# PennyMan_Ard_R3_Shield_v9_3.net
KiCad netlist of a schematic drawn in EAGLE
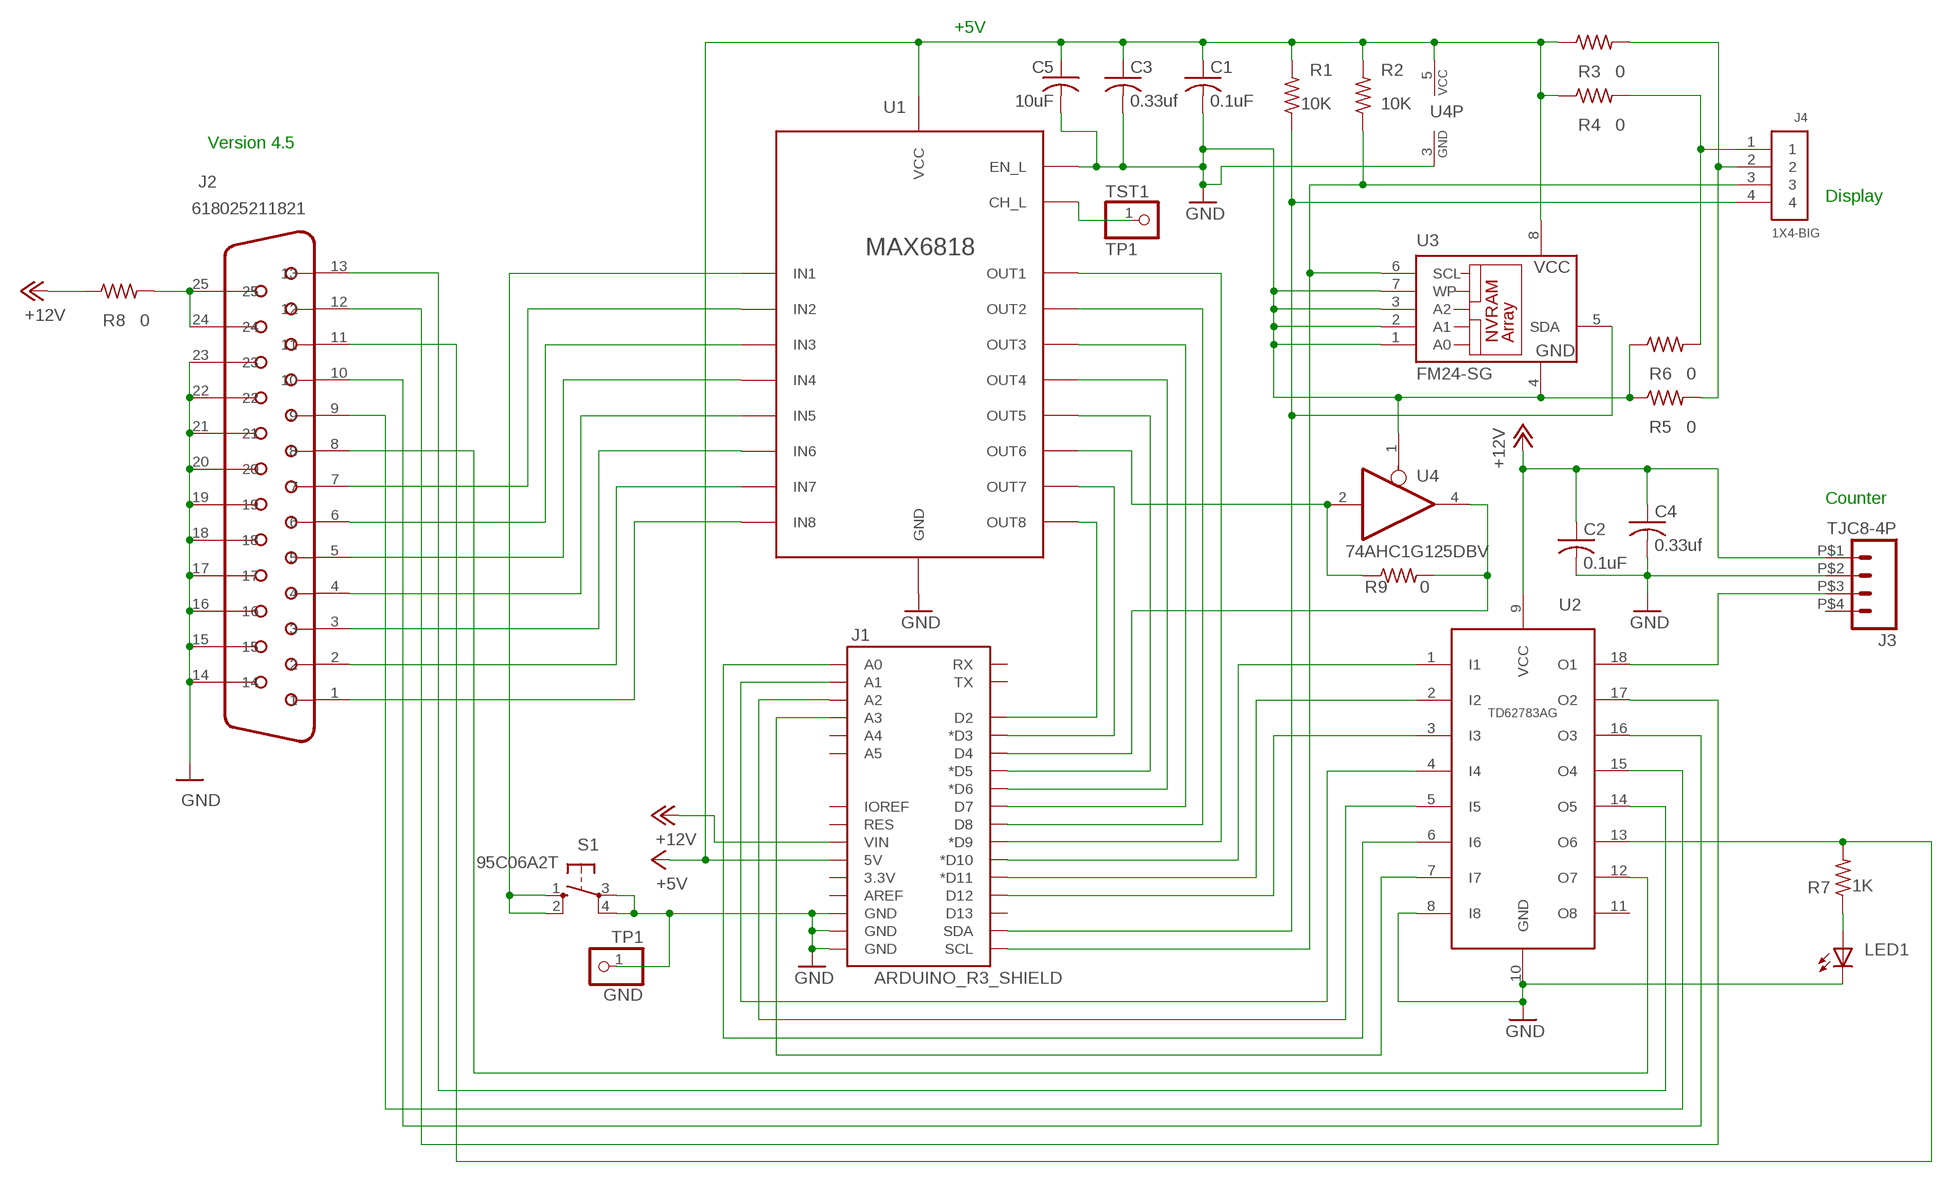
[diagram p0: schematic, sheet 1]

(export (version "E")
  (design (tool "Eeschema 10.0.6"))
  (components
    (comp (ref "C1")
      (value "0.1uF")
      (footprint "eagle-import:C0805")
      (libsource (lib "eagle-import") (part "C-USC0805"))
    )
    (comp (ref "C2")
      (value "0.1uF")
      (footprint "eagle-import:C0805")
      (libsource (lib "eagle-import") (part "C-USC0805"))
    )
    (comp (ref "C3")
      (value "0.33uf")
      (footprint "eagle-import:C1206")
      (libsource (lib "eagle-import") (part "C-USC1206"))
    )
    (comp (ref "C4")
      (value "0.33uf")
      (footprint "eagle-import:C1206")
      (libsource (lib "eagle-import") (part "C-USC1206"))
    )
    (comp (ref "C5")
      (value "10uF")
      (footprint "eagle-import:C1812")
      (libsource (lib "eagle-import") (part "C-USC1812"))
    )
    (comp (ref "GND")
      (value "TP1")
      (footprint "eagle-import:1X01")
      (libsource (lib "eagle-import") (part "PINHD-1X1"))
    )
    (comp (ref "J1")
      (value "ARDUINO_R3_SHIELD")
      (footprint "eagle-import:UNO_R3_SHIELD")
      (libsource (lib "eagle-import") (part "ARDUINO_R3_SHIELD"))
    )
    (comp (ref "J2")
      (value "618025211821")
      (footprint "eagle-import:618025211821")
      (libsource (lib "eagle-import") (part "618025211821"))
    )
    (comp (ref "J3")
      (value "TJC8-4P")
      (footprint "eagle-import:TJC8-4P")
      (libsource (lib "eagle-import") (part "TJC8-4P"))
    )
    (comp (ref "J4")
      (value "1X4-BIG")
      (footprint "eagle-import:1X04-BIG")
      (libsource (lib "eagle-import") (part "1X4-BIG"))
    )
    (comp (ref "LED1")
      (value "LEDSML0805")
      (footprint "eagle-import:SML0805")
      (libsource (lib "eagle-import") (part "LEDSML0805"))
    )
    (comp (ref "R1")
      (value "10K")
      (footprint "eagle-import:R0805")
      (libsource (lib "eagle-import") (part "R-US_R0805"))
    )
    (comp (ref "R2")
      (value "10K")
      (footprint "eagle-import:R0805")
      (libsource (lib "eagle-import") (part "R-US_R0805"))
    )
    (comp (ref "R3")
      (value "0")
      (footprint "eagle-import:R0805")
      (libsource (lib "eagle-import") (part "R-US_R0805"))
    )
    (comp (ref "R4")
      (value "0")
      (footprint "eagle-import:R0805")
      (libsource (lib "eagle-import") (part "R-US_R0805"))
    )
    (comp (ref "R5")
      (value "0")
      (footprint "eagle-import:R0805")
      (libsource (lib "eagle-import") (part "R-US_R0805"))
    )
    (comp (ref "R6")
      (value "0")
      (footprint "eagle-import:R0805")
      (libsource (lib "eagle-import") (part "R-US_R0805"))
    )
    (comp (ref "R7")
      (value "1K")
      (footprint "eagle-import:R0805")
      (libsource (lib "eagle-import") (part "R-US_R0805"))
    )
    (comp (ref "R8")
      (value "0")
      (footprint "eagle-import:R0805")
      (libsource (lib "eagle-import") (part "R-US_R0805"))
    )
    (comp (ref "R9")
      (value "0")
      (footprint "eagle-import:R0805")
      (libsource (lib "eagle-import") (part "R-US_R0805"))
    )
    (comp (ref "S1")
      (value "95C06A2T")
      (footprint "eagle-import:B3F-10XX")
      (libsource (lib "eagle-import") (part "10-XX"))
    )
    (comp (ref "TST1")
      (value "TP1")
      (footprint "eagle-import:1X01")
      (libsource (lib "eagle-import") (part "PINHD-1X1"))
    )
    (comp (ref "U1")
      (value "MAX6818")
      (footprint "eagle-import:SSOP20")
      (libsource (lib "eagle-import") (part "MAX6818"))
    )
    (comp (ref "U2")
      (value "TD62783AG")
      (footprint "eagle-import:SOP18")
      (libsource (lib "eagle-import") (part "TD62783AG"))
    )
    (comp (ref "U3")
      (value "FM24-SG")
      (footprint "eagle-import:SO8")
      (libsource (lib "eagle-import") (part "FM24-SG"))
    )
    (comp (ref "U4")
      (value "74AHC1G125DBV")
      (footprint "eagle-import:SOT23-5")
      (libsource (lib "eagle-import") (part "741G125DBVAHC"))
    )
  )
  (nets
    (net (code "1") (name "+5V") (class "Default")
      (node (ref "C1") (pin "1") (pinfunction "1_1") (pintype "passive"))
      (node (ref "C3") (pin "1") (pinfunction "1_1") (pintype "passive"))
      (node (ref "C5") (pin "1") (pinfunction "1_1") (pintype "passive"))
      (node (ref "J1") (pin "5V") (pinfunction "5V_5V") (pintype "bidirectional"))
      (node (ref "R1") (pin "2") (pinfunction "2_2") (pintype "passive"))
      (node (ref "R2") (pin "2") (pinfunction "2_2") (pintype "passive"))
      (node (ref "R3") (pin "1") (pinfunction "1_1") (pintype "passive"))
      (node (ref "R4") (pin "1") (pinfunction "1_1") (pintype "passive"))
      (node (ref "U1") (pin "VCC") (pinfunction "VCC_VCC") (pintype "bidirectional"))
      (node (ref "U3") (pin "8") (pinfunction "VCC_8") (pintype "power_in"))
      (node (ref "U4") (pin "5") (pinfunction "VCC_5") (pintype "power_in"))
    )
    (net (code "2") (name "+12V") (class "Default")
      (node (ref "C2") (pin "1") (pinfunction "1_1") (pintype "passive"))
      (node (ref "C4") (pin "1") (pinfunction "1_1") (pintype "passive"))
      (node (ref "J1") (pin "VIN") (pinfunction "VIN_VIN") (pintype "bidirectional"))
      (node (ref "J3") (pin "P$1") (pinfunction "1_P$1") (pintype "passive"))
      (node (ref "R8") (pin "1") (pinfunction "1_1") (pintype "passive"))
      (node (ref "U2") (pin "9") (pinfunction "VCC_9") (pintype "bidirectional"))
    )
    (net (code "3") (name "GND") (class "Default")
      (node (ref "C1") (pin "2") (pinfunction "2_2") (pintype "passive"))
      (node (ref "C2") (pin "2") (pinfunction "2_2") (pintype "passive"))
      (node (ref "C3") (pin "2") (pinfunction "2_2") (pintype "passive"))
      (node (ref "C4") (pin "2") (pinfunction "2_2") (pintype "passive"))
      (node (ref "C5") (pin "2") (pinfunction "2_2") (pintype "passive"))
      (node (ref "GND") (pin "1") (pinfunction "1_1") (pintype "passive"))
      (node (ref "J1") (pin "GND@0") (pinfunction "GND_GND@0") (pintype "bidirectional"))
      (node (ref "J1") (pin "GND@1") (pinfunction "GND_GND@1") (pintype "bidirectional"))
      (node (ref "J1") (pin "GND@2") (pinfunction "GND_GND@2") (pintype "bidirectional"))
      (node (ref "J2") (pin "14") (pinfunction "14_14") (pintype "bidirectional"))
      (node (ref "J2") (pin "15") (pinfunction "15_15") (pintype "bidirectional"))
      (node (ref "J2") (pin "16") (pinfunction "16_16") (pintype "bidirectional"))
      (node (ref "J2") (pin "17") (pinfunction "17_17") (pintype "bidirectional"))
      (node (ref "J2") (pin "18") (pinfunction "18_18") (pintype "bidirectional"))
      (node (ref "J2") (pin "19") (pinfunction "19_19") (pintype "bidirectional"))
      (node (ref "J2") (pin "20") (pinfunction "20_20") (pintype "bidirectional"))
      (node (ref "J2") (pin "21") (pinfunction "21_21") (pintype "bidirectional"))
      (node (ref "J2") (pin "22") (pinfunction "22_22") (pintype "bidirectional"))
      (node (ref "J2") (pin "23") (pinfunction "23_23") (pintype "bidirectional"))
      (node (ref "J3") (pin "P$2") (pinfunction "2_P$2") (pintype "passive"))
      (node (ref "LED1") (pin "C") (pinfunction "C_C") (pintype "passive"))
      (node (ref "R5") (pin "1") (pinfunction "1_1") (pintype "passive"))
      (node (ref "R6") (pin "1") (pinfunction "1_1") (pintype "passive"))
      (node (ref "S1") (pin "3") (pinfunction "P_3") (pintype "passive"))
      (node (ref "S1") (pin "4") (pinfunction "P1_4") (pintype "passive"))
      (node (ref "U1") (pin "EN_L") (pinfunction "EN_L_EN_L") (pintype "bidirectional"))
      (node (ref "U1") (pin "GND") (pinfunction "GND_GND") (pintype "bidirectional"))
      (node (ref "U2") (pin "10") (pinfunction "GND_10") (pintype "bidirectional"))
      (node (ref "U2") (pin "8") (pinfunction "I8_8") (pintype "bidirectional"))
      (node (ref "U3") (pin "1") (pinfunction "A0_1") (pintype "passive"))
      (node (ref "U3") (pin "2") (pinfunction "A1_2") (pintype "passive"))
      (node (ref "U3") (pin "3") (pinfunction "A2_3") (pintype "passive"))
      (node (ref "U3") (pin "4") (pinfunction "GND_4") (pintype "power_in"))
      (node (ref "U3") (pin "7") (pinfunction "WP_7") (pintype "input"))
      (node (ref "U4") (pin "1") (pinfunction "OE_1") (pintype "input"))
      (node (ref "U4") (pin "3") (pinfunction "GND_3") (pintype "power_in"))
    )
    (net (code "4") (name "Net-(J1-*D3)") (class "Default")
      (node (ref "J1") (pin "D3") (pinfunction "*D3_D3") (pintype "bidirectional"))
      (node (ref "U1") (pin "OUT7") (pinfunction "OUT7_OUT7") (pintype "bidirectional"))
    )
    (net (code "5") (name "Net-(J1-*D5)") (class "Default")
      (node (ref "J1") (pin "D5") (pinfunction "*D5_D5") (pintype "bidirectional"))
      (node (ref "U1") (pin "OUT5") (pinfunction "OUT5_OUT5") (pintype "bidirectional"))
    )
    (net (code "6") (name "Net-(J1-*D6)") (class "Default")
      (node (ref "J1") (pin "D6") (pinfunction "*D6_D6") (pintype "bidirectional"))
      (node (ref "U1") (pin "OUT4") (pinfunction "OUT4_OUT4") (pintype "bidirectional"))
    )
    (net (code "7") (name "Net-(J1-*D9)") (class "Default")
      (node (ref "J1") (pin "D9") (pinfunction "*D9_D9") (pintype "bidirectional"))
      (node (ref "U1") (pin "OUT1") (pinfunction "OUT1_OUT1") (pintype "bidirectional"))
    )
    (net (code "8") (name "Net-(J1-*D10)") (class "Default")
      (node (ref "J1") (pin "D10") (pinfunction "*D10_D10") (pintype "bidirectional"))
      (node (ref "U2") (pin "1") (pinfunction "I1_1") (pintype "bidirectional"))
    )
    (net (code "9") (name "Net-(J1-*D11)") (class "Default")
      (node (ref "J1") (pin "D11") (pinfunction "*D11_D11") (pintype "bidirectional"))
      (node (ref "U2") (pin "2") (pinfunction "I2_2") (pintype "bidirectional"))
    )
    (net (code "10") (name "Net-(J1-PadD2)") (class "Default")
      (node (ref "J1") (pin "D2") (pinfunction "D2_D2") (pintype "bidirectional"))
      (node (ref "U1") (pin "OUT8") (pinfunction "OUT8_OUT8") (pintype "bidirectional"))
    )
    (net (code "11") (name "Net-(J1-PadD7)") (class "Default")
      (node (ref "J1") (pin "D7") (pinfunction "D7_D7") (pintype "bidirectional"))
      (node (ref "U1") (pin "OUT3") (pinfunction "OUT3_OUT3") (pintype "bidirectional"))
    )
    (net (code "12") (name "Net-(J1-PadD8)") (class "Default")
      (node (ref "J1") (pin "D8") (pinfunction "D8_D8") (pintype "bidirectional"))
      (node (ref "U1") (pin "OUT2") (pinfunction "OUT2_OUT2") (pintype "bidirectional"))
    )
    (net (code "13") (name "Net-(J2-Pad1)") (class "Default")
      (node (ref "J2") (pin "1") (pinfunction "1_1") (pintype "bidirectional"))
      (node (ref "U1") (pin "IN8") (pinfunction "IN8_IN8") (pintype "bidirectional"))
    )
    (net (code "14") (name "Net-(J2-Pad2)") (class "Default")
      (node (ref "J2") (pin "2") (pinfunction "2_2") (pintype "bidirectional"))
      (node (ref "U1") (pin "IN7") (pinfunction "IN7_IN7") (pintype "bidirectional"))
    )
    (net (code "15") (name "Net-(J2-Pad3)") (class "Default")
      (node (ref "J2") (pin "3") (pinfunction "3_3") (pintype "bidirectional"))
      (node (ref "U1") (pin "IN6") (pinfunction "IN6_IN6") (pintype "bidirectional"))
    )
    (net (code "16") (name "Net-(J2-Pad4)") (class "Default")
      (node (ref "J2") (pin "4") (pinfunction "4_4") (pintype "bidirectional"))
      (node (ref "U1") (pin "IN5") (pinfunction "IN5_IN5") (pintype "bidirectional"))
    )
    (net (code "17") (name "Net-(J2-Pad5)") (class "Default")
      (node (ref "J2") (pin "5") (pinfunction "5_5") (pintype "bidirectional"))
      (node (ref "U1") (pin "IN4") (pinfunction "IN4_IN4") (pintype "bidirectional"))
    )
    (net (code "18") (name "Net-(J2-Pad6)") (class "Default")
      (node (ref "J2") (pin "6") (pinfunction "6_6") (pintype "bidirectional"))
      (node (ref "U1") (pin "IN3") (pinfunction "IN3_IN3") (pintype "bidirectional"))
    )
    (net (code "19") (name "Net-(J2-Pad7)") (class "Default")
      (node (ref "J2") (pin "7") (pinfunction "7_7") (pintype "bidirectional"))
      (node (ref "U1") (pin "IN2") (pinfunction "IN2_IN2") (pintype "bidirectional"))
    )
    (net (code "20") (name "Net-(J2-Pad24)") (class "Default")
      (node (ref "J2") (pin "24") (pinfunction "24_24") (pintype "bidirectional"))
      (node (ref "J2") (pin "25") (pinfunction "25_25") (pintype "bidirectional"))
      (node (ref "R8") (pin "2") (pinfunction "2_2") (pintype "passive"))
    )
    (net (code "21") (name "Net-(J3-3)") (class "Default")
      (node (ref "J3") (pin "P$3") (pinfunction "3_P$3") (pintype "passive"))
      (node (ref "U2") (pin "18") (pinfunction "O1_18") (pintype "bidirectional"))
    )
    (net (code "22") (name "Net-(J4-Pad1)") (class "Default")
      (node (ref "J4") (pin "1") (pinfunction "1_1") (pintype "bidirectional"))
      (node (ref "R4") (pin "2") (pinfunction "2_2") (pintype "passive"))
      (node (ref "R6") (pin "2") (pinfunction "2_2") (pintype "passive"))
    )
    (net (code "23") (name "Net-(J4-Pad2)") (class "Default")
      (node (ref "J4") (pin "2") (pinfunction "2_2") (pintype "bidirectional"))
      (node (ref "R3") (pin "2") (pinfunction "2_2") (pintype "passive"))
      (node (ref "R5") (pin "2") (pinfunction "2_2") (pintype "passive"))
    )
    (net (code "24") (name "Net-(LED1-PadA)") (class "Default")
      (node (ref "LED1") (pin "A") (pinfunction "A_A") (pintype "passive"))
      (node (ref "R7") (pin "1") (pinfunction "1_1") (pintype "passive"))
    )
    (net (code "25") (name "Net-(S1-S)") (class "Default")
      (node (ref "S1") (pin "1") (pinfunction "S_1") (pintype "passive"))
      (node (ref "S1") (pin "2") (pinfunction "S1_2") (pintype "passive"))
      (node (ref "U1") (pin "IN1") (pinfunction "IN1_IN1") (pintype "bidirectional"))
    )
    (net (code "26") (name "Net-(TST1-Pad1)") (class "Default")
      (node (ref "TST1") (pin "1") (pinfunction "1_1") (pintype "passive"))
      (node (ref "U1") (pin "CH_L") (pinfunction "CH_L_CH_L") (pintype "bidirectional"))
    )
    (net (code "27") (name "Net-(U2-I3)") (class "Default")
      (node (ref "J1") (pin "D12") (pinfunction "D12_D12") (pintype "bidirectional"))
      (node (ref "U2") (pin "3") (pinfunction "I3_3") (pintype "bidirectional"))
    )
    (net (code "28") (name "Net-(U2-I4)") (class "Default")
      (node (ref "J1") (pin "A1") (pinfunction "A1_A1") (pintype "bidirectional"))
      (node (ref "U2") (pin "4") (pinfunction "I4_4") (pintype "bidirectional"))
    )
    (net (code "29") (name "Net-(U2-I5)") (class "Default")
      (node (ref "J1") (pin "A2") (pinfunction "A2_A2") (pintype "bidirectional"))
      (node (ref "U2") (pin "5") (pinfunction "I5_5") (pintype "bidirectional"))
    )
    (net (code "30") (name "Net-(U2-I6)") (class "Default")
      (node (ref "J1") (pin "A0") (pinfunction "A0_A0") (pintype "bidirectional"))
      (node (ref "U2") (pin "6") (pinfunction "I6_6") (pintype "bidirectional"))
    )
    (net (code "31") (name "Net-(U2-I7)") (class "Default")
      (node (ref "J1") (pin "A3") (pinfunction "A3_A3") (pintype "bidirectional"))
      (node (ref "U2") (pin "7") (pinfunction "I7_7") (pintype "bidirectional"))
    )
    (net (code "32") (name "Net-(U2-O2)") (class "Default")
      (node (ref "J2") (pin "12") (pinfunction "12_12") (pintype "bidirectional"))
      (node (ref "U2") (pin "17") (pinfunction "O2_17") (pintype "bidirectional"))
    )
    (net (code "33") (name "Net-(U2-O3)") (class "Default")
      (node (ref "J2") (pin "10") (pinfunction "10_10") (pintype "bidirectional"))
      (node (ref "U2") (pin "16") (pinfunction "O3_16") (pintype "bidirectional"))
    )
    (net (code "34") (name "Net-(U2-O4)") (class "Default")
      (node (ref "J2") (pin "9") (pinfunction "9_9") (pintype "bidirectional"))
      (node (ref "U2") (pin "15") (pinfunction "O4_15") (pintype "bidirectional"))
    )
    (net (code "35") (name "Net-(U2-O5)") (class "Default")
      (node (ref "J2") (pin "13") (pinfunction "13_13") (pintype "bidirectional"))
      (node (ref "U2") (pin "14") (pinfunction "O5_14") (pintype "bidirectional"))
    )
    (net (code "36") (name "Net-(U2-O6)") (class "Default")
      (node (ref "J2") (pin "11") (pinfunction "11_11") (pintype "bidirectional"))
      (node (ref "R7") (pin "2") (pinfunction "2_2") (pintype "passive"))
      (node (ref "U2") (pin "13") (pinfunction "O6_13") (pintype "bidirectional"))
    )
    (net (code "37") (name "Net-(U2-O7)") (class "Default")
      (node (ref "J2") (pin "8") (pinfunction "8_8") (pintype "bidirectional"))
      (node (ref "U2") (pin "12") (pinfunction "O7_12") (pintype "bidirectional"))
    )
    (net (code "38") (name "Net-(U3-SCL)") (class "Default")
      (node (ref "J1") (pin "SCL") (pinfunction "SCL_SCL") (pintype "bidirectional"))
      (node (ref "J4") (pin "3") (pinfunction "3_3") (pintype "bidirectional"))
      (node (ref "R2") (pin "1") (pinfunction "1_1") (pintype "passive"))
      (node (ref "U3") (pin "6") (pinfunction "SCL_6") (pintype "input"))
    )
    (net (code "39") (name "Net-(U3-SDA)") (class "Default")
      (node (ref "J1") (pin "SDA") (pinfunction "SDA_SDA") (pintype "bidirectional"))
      (node (ref "J4") (pin "4") (pinfunction "4_4") (pintype "bidirectional"))
      (node (ref "R1") (pin "1") (pinfunction "1_1") (pintype "passive"))
      (node (ref "U3") (pin "5") (pinfunction "SDA_5") (pintype "bidirectional"))
    )
    (net (code "40") (name "Net-(U4A-I)") (class "Default")
      (node (ref "R9") (pin "1") (pinfunction "1_1") (pintype "passive"))
      (node (ref "U1") (pin "OUT6") (pinfunction "OUT6_OUT6") (pintype "bidirectional"))
      (node (ref "U4") (pin "2") (pinfunction "I_2") (pintype "input"))
    )
    (net (code "41") (name "Net-(U4A-O)") (class "Default")
      (node (ref "J1") (pin "D4") (pinfunction "D4_D4") (pintype "bidirectional"))
      (node (ref "R9") (pin "2") (pinfunction "2_2") (pintype "passive"))
      (node (ref "U4") (pin "4") (pinfunction "O_4") (pintype "tri_state"))
    )
    (net (code "42") (name "unconnected-(J1-Pad3.3V)") (class "Default")
      (node (ref "J1") (pin "3.3V") (pinfunction "3.3V_3.3V") (pintype "bidirectional"))
    )
    (net (code "43") (name "unconnected-(J1-PadA4)") (class "Default")
      (node (ref "J1") (pin "A4") (pinfunction "A4_A4") (pintype "bidirectional"))
    )
    (net (code "44") (name "unconnected-(J1-PadA5)") (class "Default")
      (node (ref "J1") (pin "A5") (pinfunction "A5_A5") (pintype "bidirectional"))
    )
    (net (code "45") (name "unconnected-(J1-PadAREF)") (class "Default")
      (node (ref "J1") (pin "AREF") (pinfunction "AREF_AREF") (pintype "bidirectional"))
    )
    (net (code "46") (name "unconnected-(J1-PadD13)") (class "Default")
      (node (ref "J1") (pin "D13") (pinfunction "D13_D13") (pintype "bidirectional"))
    )
    (net (code "47") (name "unconnected-(J1-PadIOREF)") (class "Default")
      (node (ref "J1") (pin "IOREF") (pinfunction "IOREF_IOREF") (pintype "bidirectional"))
    )
    (net (code "48") (name "unconnected-(J1-PadRES)") (class "Default")
      (node (ref "J1") (pin "RES") (pinfunction "RES_RES") (pintype "bidirectional"))
    )
    (net (code "49") (name "unconnected-(J1-PadRX)") (class "Default")
      (node (ref "J1") (pin "RX") (pinfunction "RX_RX") (pintype "bidirectional"))
    )
    (net (code "50") (name "unconnected-(J1-PadTX)") (class "Default")
      (node (ref "J1") (pin "TX") (pinfunction "TX_TX") (pintype "bidirectional"))
    )
    (net (code "51") (name "unconnected-(J3-4-PadP$4)") (class "Default")
      (node (ref "J3") (pin "P$4") (pinfunction "4_P$4") (pintype "passive"))
    )
    (net (code "52") (name "unconnected-(U2-O8-Pad11)") (class "Default")
      (node (ref "U2") (pin "11") (pinfunction "O8_11") (pintype "bidirectional"))
    )
  )
)
